# ComsoftFixV4_Finished_Draft_Labeled_Comp.net
KiCad netlist of a schematic drawn in EAGLE
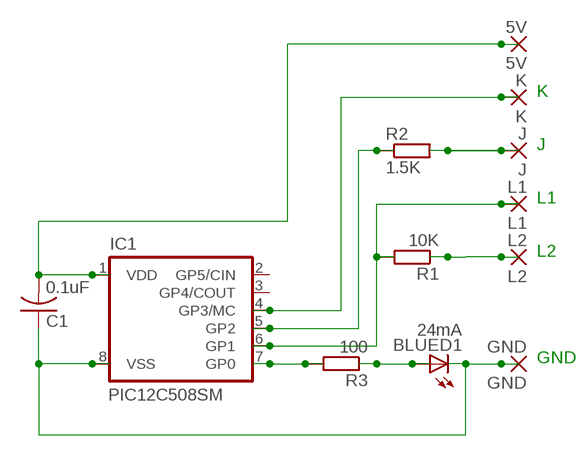
[diagram p0: schematic, sheet 1]

(export (version "E")
  (design (tool "Eeschema 10.0.6"))
  (components
    (comp (ref "5V")
      (value "5V")
      (footprint "eagle-import:SMD1,27-2,54")
      (libsource (lib "eagle-import") (part "WIREPADSMD1,27-254"))
    )
    (comp (ref "BLUED1")
      (value "24mA")
      (footprint "eagle-import:CHIPLED_0603")
      (libsource (lib "eagle-import") (part "LEDCHIPLED_0603"))
    )
    (comp (ref "C1")
      (value "0.1uF")
      (footprint "eagle-import:C0603")
      (libsource (lib "eagle-import") (part "C-USC0603"))
    )
    (comp (ref "GND")
      (value "GND")
      (footprint "eagle-import:SMD1,27-2,54")
      (libsource (lib "eagle-import") (part "WIREPADSMD1,27-254"))
    )
    (comp (ref "IC1")
      (value "PIC12C508SM")
      (footprint "eagle-import:SO-08M")
      (libsource (lib "eagle-import") (part "PIC12C?SM508"))
    )
    (comp (ref "J")
      (value "J")
      (footprint "eagle-import:SMD1,27-2,54")
      (libsource (lib "eagle-import") (part "WIREPADSMD1,27-254"))
    )
    (comp (ref "K")
      (value "K")
      (footprint "eagle-import:SMD1,27-2,54")
      (libsource (lib "eagle-import") (part "WIREPADSMD1,27-254"))
    )
    (comp (ref "L1")
      (value "L1")
      (footprint "eagle-import:SMD1,27-2,54")
      (libsource (lib "eagle-import") (part "WIREPADSMD1,27-254"))
    )
    (comp (ref "L2")
      (value "L2")
      (footprint "eagle-import:SMD1,27-2,54")
      (libsource (lib "eagle-import") (part "WIREPADSMD1,27-254"))
    )
    (comp (ref "R1")
      (value "10K")
      (footprint "eagle-import:R0603")
      (libsource (lib "eagle-import") (part "R-EU_R0603"))
    )
    (comp (ref "R2")
      (value "1.5K")
      (footprint "eagle-import:R0603")
      (libsource (lib "eagle-import") (part "R-EU_R0603"))
    )
    (comp (ref "R3")
      (value "100")
      (footprint "eagle-import:R0603")
      (libsource (lib "eagle-import") (part "R-EU_R0603"))
    )
  )
  (nets
    (net (code "1") (name "Net-(5V-P)") (class "Default")
      (node (ref "5V") (pin "1") (pinfunction "P_1") (pintype "passive"))
      (node (ref "C1") (pin "2") (pinfunction "2_2") (pintype "passive"))
      (node (ref "IC1") (pin "1") (pinfunction "VDD_1") (pintype "power_in"))
    )
    (net (code "2") (name "Net-(BLUED1-PadA)") (class "Default")
      (node (ref "BLUED1") (pin "A") (pinfunction "A_A") (pintype "passive"))
      (node (ref "R3") (pin "1") (pinfunction "1_1") (pintype "passive"))
    )
    (net (code "3") (name "Net-(GND-P)") (class "Default")
      (node (ref "BLUED1") (pin "C") (pinfunction "C_C") (pintype "passive"))
      (node (ref "C1") (pin "1") (pinfunction "1_1") (pintype "passive"))
      (node (ref "GND") (pin "1") (pinfunction "P_1") (pintype "passive"))
      (node (ref "IC1") (pin "8") (pinfunction "VSS_8") (pintype "power_in"))
    )
    (net (code "4") (name "Net-(IC1-GP0)") (class "Default")
      (node (ref "IC1") (pin "7") (pinfunction "GP0_7") (pintype "bidirectional"))
      (node (ref "R3") (pin "2") (pinfunction "2_2") (pintype "passive"))
    )
    (net (code "5") (name "Net-(IC1-GP1)") (class "Default")
      (node (ref "IC1") (pin "6") (pinfunction "GP1_6") (pintype "bidirectional"))
      (node (ref "L1") (pin "1") (pinfunction "P_1") (pintype "passive"))
      (node (ref "R1") (pin "2") (pinfunction "2_2") (pintype "passive"))
    )
    (net (code "6") (name "Net-(IC1-GP2)") (class "Default")
      (node (ref "IC1") (pin "5") (pinfunction "GP2_5") (pintype "bidirectional"))
      (node (ref "R2") (pin "1") (pinfunction "1_1") (pintype "passive"))
    )
    (net (code "7") (name "Net-(IC1-GP3{slash}MC)") (class "Default")
      (node (ref "IC1") (pin "4") (pinfunction "GP3/MC_4") (pintype "input"))
      (node (ref "K") (pin "1") (pinfunction "P_1") (pintype "passive"))
    )
    (net (code "8") (name "Net-(J-P)") (class "Default")
      (node (ref "J") (pin "1") (pinfunction "P_1") (pintype "passive"))
      (node (ref "R2") (pin "2") (pinfunction "2_2") (pintype "passive"))
    )
    (net (code "9") (name "Net-(L2-P)") (class "Default")
      (node (ref "L2") (pin "1") (pinfunction "P_1") (pintype "passive"))
      (node (ref "R1") (pin "1") (pinfunction "1_1") (pintype "passive"))
    )
    (net (code "10") (name "unconnected-(IC1-GP4{slash}COUT-Pad3)") (class "Default")
      (node (ref "IC1") (pin "3") (pinfunction "GP4/COUT_3") (pintype "bidirectional"))
    )
    (net (code "11") (name "unconnected-(IC1-GP5{slash}CIN-Pad2)") (class "Default")
      (node (ref "IC1") (pin "2") (pinfunction "GP5/CIN_2") (pintype "bidirectional"))
    )
  )
)
